# EthernetModule.net
KiCad netlist of a schematic drawn in EasyEDA Pro
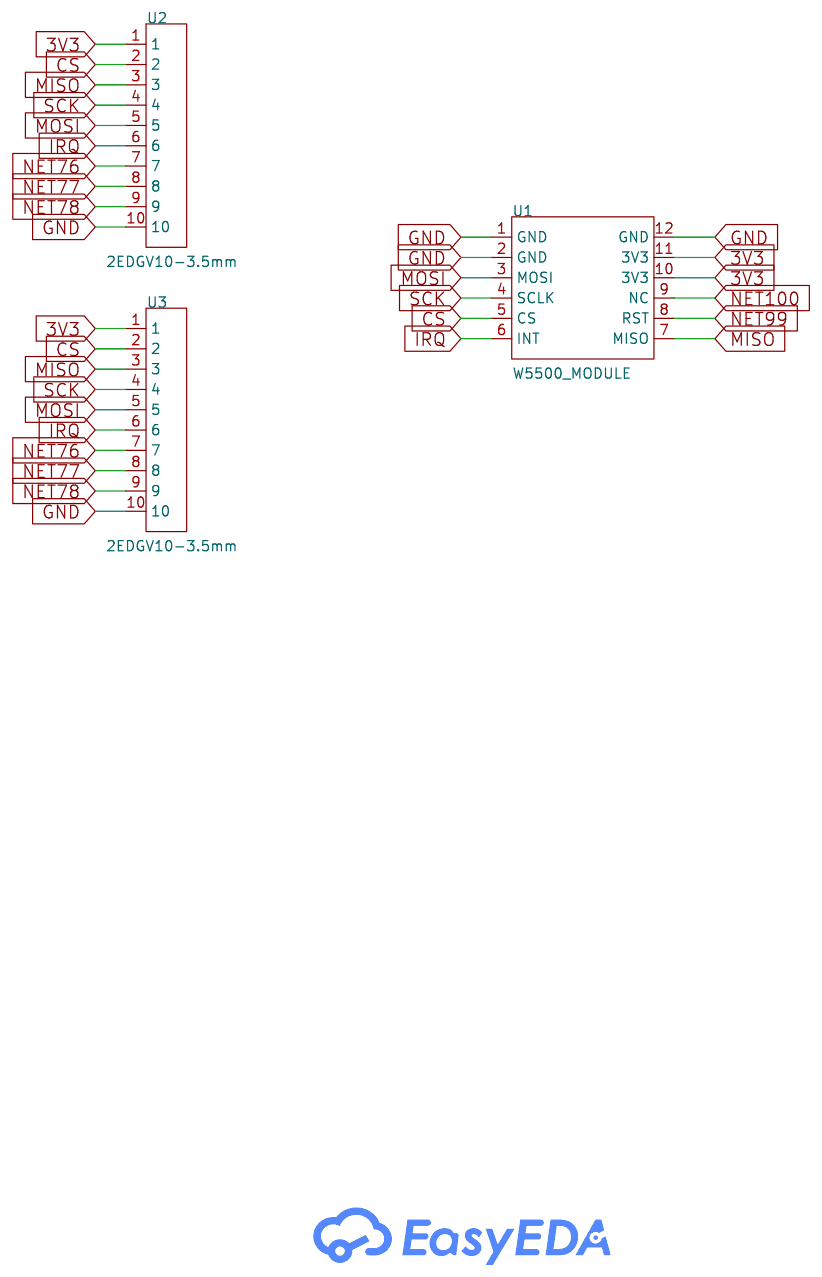
[diagram p0: schematic sheet]

(export (version "E")
  (design (tool "Eeschema 10.0.6"))
  (components
    (comp (ref "U1")
      (value "W5500_MODULE")
      (footprint "easyedapro:COMM-TH_L25.0-W23.0_W5500_MODULE")
      (libsource (lib "easyedapro") (part "W5500_MODULE_LAN"))
    )
    (comp (ref "U2")
      (value "2EDGV10-3.5mm")
      (footprint "easyedapro:CONN-TH_10P-P3.50")
      (libsource (lib "easyedapro") (part "CONN-TH_10P-P3.50"))
    )
    (comp (ref "U3")
      (value "2EDGV10-3.5mm")
      (footprint "easyedapro:CONN-TH_10P-P3.50")
      (libsource (lib "easyedapro") (part "CONN-TH_10P-P3.50"))
    )
  )
  (nets
    (net (code "1") (name "3V3") (class "Default")
      (node (ref "U1") (pin "10") (pinfunction "3V3_10") (pintype "unspecified"))
      (node (ref "U1") (pin "11") (pinfunction "3V3_11") (pintype "unspecified"))
      (node (ref "U2") (pin "1") (pinfunction "1_1") (pintype "unspecified"))
      (node (ref "U3") (pin "1") (pinfunction "1_1") (pintype "unspecified"))
    )
    (net (code "2") (name "CS") (class "Default")
      (node (ref "U1") (pin "5") (pinfunction "CS_5") (pintype "unspecified"))
      (node (ref "U2") (pin "2") (pinfunction "2_2") (pintype "unspecified"))
      (node (ref "U3") (pin "2") (pinfunction "2_2") (pintype "unspecified"))
    )
    (net (code "3") (name "GND") (class "Default")
      (node (ref "U1") (pin "1") (pinfunction "GND_1") (pintype "unspecified"))
      (node (ref "U1") (pin "12") (pinfunction "GND_12") (pintype "unspecified"))
      (node (ref "U1") (pin "2") (pinfunction "GND_2") (pintype "unspecified"))
      (node (ref "U2") (pin "10") (pinfunction "10_10") (pintype "unspecified"))
      (node (ref "U3") (pin "10") (pinfunction "10_10") (pintype "unspecified"))
    )
    (net (code "4") (name "IRQ") (class "Default")
      (node (ref "U1") (pin "6") (pinfunction "INT_6") (pintype "unspecified"))
      (node (ref "U2") (pin "6") (pinfunction "6_6") (pintype "unspecified"))
      (node (ref "U3") (pin "6") (pinfunction "6_6") (pintype "unspecified"))
    )
    (net (code "5") (name "MISO") (class "Default")
      (node (ref "U1") (pin "7") (pinfunction "MISO_7") (pintype "unspecified"))
      (node (ref "U2") (pin "3") (pinfunction "3_3") (pintype "unspecified"))
      (node (ref "U3") (pin "3") (pinfunction "3_3") (pintype "unspecified"))
    )
    (net (code "6") (name "MOSI") (class "Default")
      (node (ref "U1") (pin "3") (pinfunction "MOSI_3") (pintype "unspecified"))
      (node (ref "U2") (pin "5") (pinfunction "5_5") (pintype "unspecified"))
      (node (ref "U3") (pin "5") (pinfunction "5_5") (pintype "unspecified"))
    )
    (net (code "7") (name "NET76") (class "Default")
      (node (ref "U2") (pin "7") (pinfunction "7_7") (pintype "unspecified"))
      (node (ref "U3") (pin "7") (pinfunction "7_7") (pintype "unspecified"))
    )
    (net (code "8") (name "NET77") (class "Default")
      (node (ref "U2") (pin "8") (pinfunction "8_8") (pintype "unspecified"))
      (node (ref "U3") (pin "8") (pinfunction "8_8") (pintype "unspecified"))
    )
    (net (code "9") (name "NET78") (class "Default")
      (node (ref "U2") (pin "9") (pinfunction "9_9") (pintype "unspecified"))
      (node (ref "U3") (pin "9") (pinfunction "9_9") (pintype "unspecified"))
    )
    (net (code "10") (name "NET99") (class "Default")
      (node (ref "U1") (pin "8") (pinfunction "RST_8") (pintype "unspecified"))
    )
    (net (code "11") (name "NET100") (class "Default")
      (node (ref "U1") (pin "9") (pinfunction "NC_9") (pintype "unspecified"))
    )
    (net (code "12") (name "SCK") (class "Default")
      (node (ref "U1") (pin "4") (pinfunction "SCLK_4") (pintype "unspecified"))
      (node (ref "U2") (pin "4") (pinfunction "4_4") (pintype "unspecified"))
      (node (ref "U3") (pin "4") (pinfunction "4_4") (pintype "unspecified"))
    )
  )
)
